# MuffinSchematic.net
KiCad netlist of a schematic drawn in EasyEDA
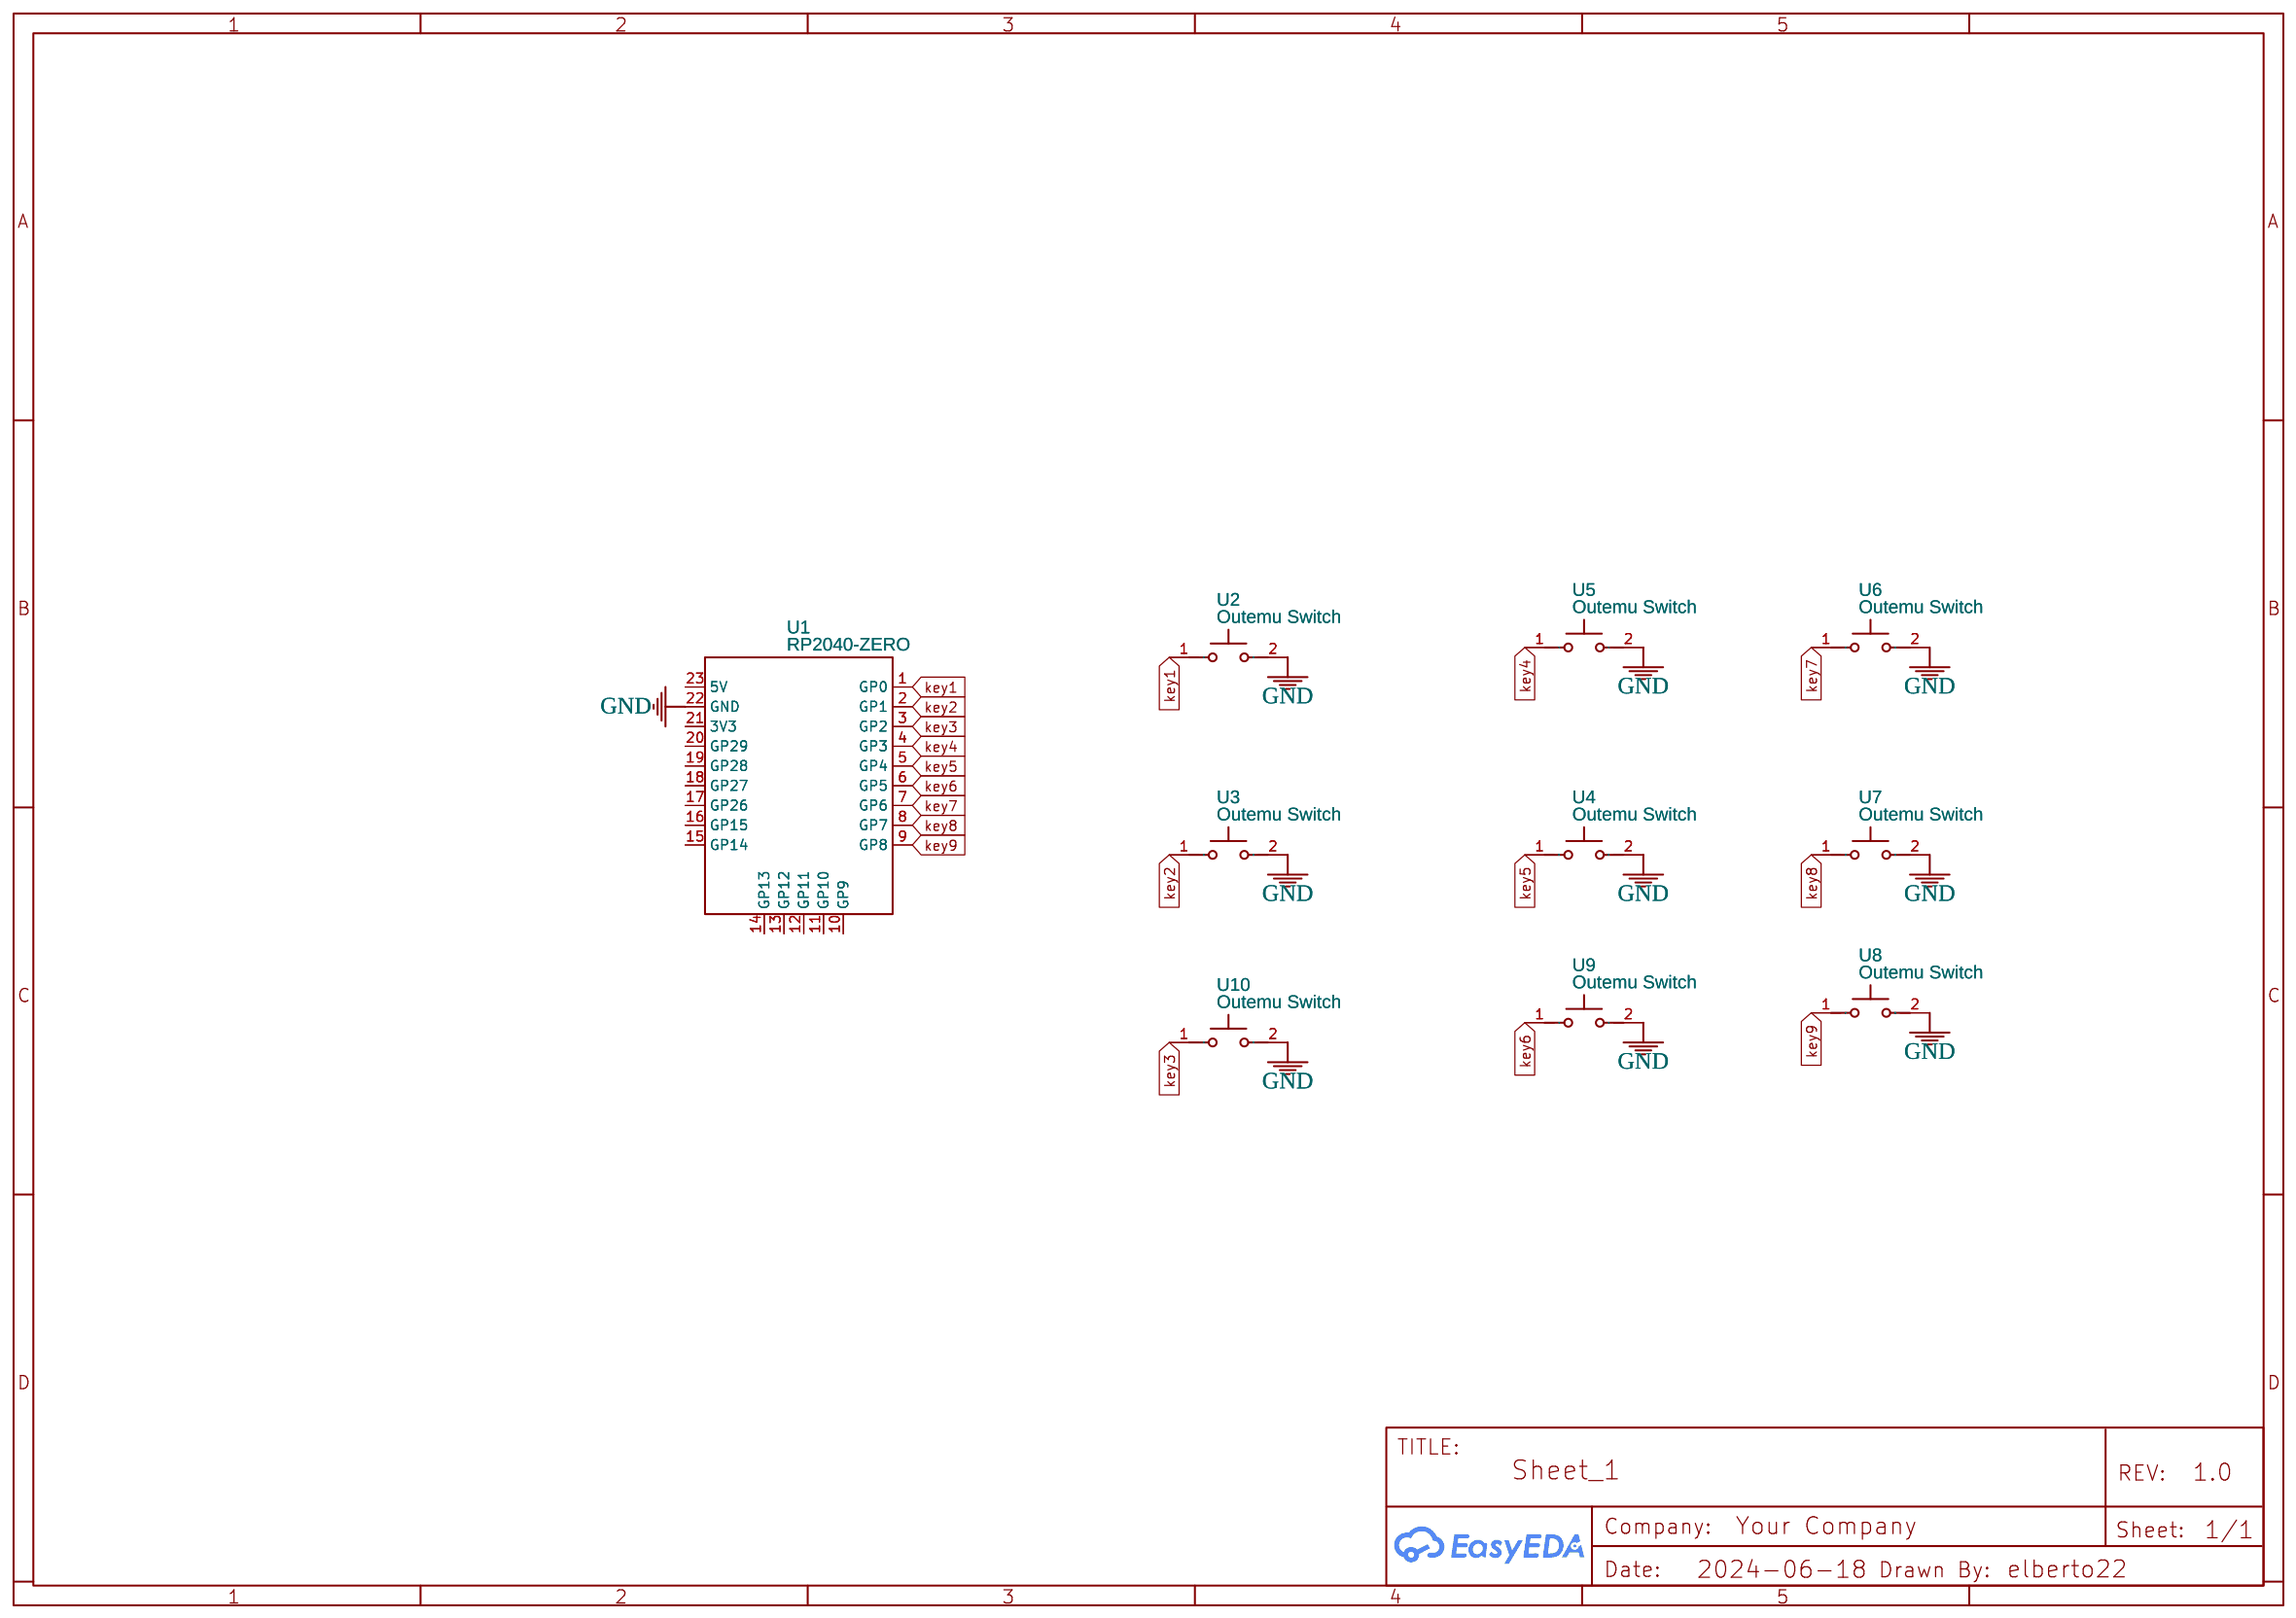
[diagram p0: schematic sheet]

(export (version "E")
  (design (tool "Eeschema 10.0.6"))
  (components
    (comp (ref "U1")
      (value "RP2040-ZERO")
      (fields
        (field (name "Manufacturer Part") "RP2040-Zero")
        (field (name "Manufacturer") "Waveshare(微雪电子)")
      )
      (libsource (lib "") (part "RP2040-ZERO"))
    )
    (comp (ref "U2")
      (value "Outemu Switch")
      (fields (field (name "Manufacturer") "HepLer"))
      (libsource (lib "") (part "Outemu Switch"))
    )
    (comp (ref "U3")
      (value "Outemu Switch")
      (fields (field (name "Manufacturer") "HepLer"))
      (libsource (lib "") (part "Outemu Switch"))
    )
    (comp (ref "U4")
      (value "Outemu Switch")
      (fields (field (name "Manufacturer") "HepLer"))
      (libsource (lib "") (part "Outemu Switch"))
    )
    (comp (ref "U5")
      (value "Outemu Switch")
      (fields (field (name "Manufacturer") "HepLer"))
      (libsource (lib "") (part "Outemu Switch"))
    )
    (comp (ref "U6")
      (value "Outemu Switch")
      (fields (field (name "Manufacturer") "HepLer"))
      (libsource (lib "") (part "Outemu Switch"))
    )
    (comp (ref "U7")
      (value "Outemu Switch")
      (fields (field (name "Manufacturer") "HepLer"))
      (libsource (lib "") (part "Outemu Switch"))
    )
    (comp (ref "U8")
      (value "Outemu Switch")
      (fields (field (name "Manufacturer") "HepLer"))
      (libsource (lib "") (part "Outemu Switch"))
    )
    (comp (ref "U9")
      (value "Outemu Switch")
      (fields (field (name "Manufacturer") "HepLer"))
      (libsource (lib "") (part "Outemu Switch"))
    )
    (comp (ref "U10")
      (value "Outemu Switch")
      (fields (field (name "Manufacturer") "HepLer"))
      (libsource (lib "") (part "Outemu Switch"))
    )
  )
  (nets
    (net (code "1") (name "GND") (class "Default")
      (node (ref "U1") (pin "22") (pinfunction "GND_22") (pintype "unspecified"))
      (node (ref "U10") (pin "2") (pinfunction "2_2") (pintype "unspecified"))
      (node (ref "U2") (pin "2") (pinfunction "2_2") (pintype "unspecified"))
      (node (ref "U3") (pin "2") (pinfunction "2_2") (pintype "unspecified"))
      (node (ref "U4") (pin "2") (pinfunction "2_2") (pintype "unspecified"))
      (node (ref "U5") (pin "2") (pinfunction "2_2") (pintype "unspecified"))
      (node (ref "U6") (pin "2") (pinfunction "2_2") (pintype "unspecified"))
      (node (ref "U7") (pin "2") (pinfunction "2_2") (pintype "unspecified"))
      (node (ref "U8") (pin "2") (pinfunction "2_2") (pintype "unspecified"))
      (node (ref "U9") (pin "2") (pinfunction "2_2") (pintype "unspecified"))
    )
    (net (code "2") (name "key1") (class "Default")
      (node (ref "U1") (pin "1") (pinfunction "GP0_1") (pintype "unspecified"))
      (node (ref "U2") (pin "1") (pinfunction "1_1") (pintype "unspecified"))
    )
    (net (code "3") (name "key2") (class "Default")
      (node (ref "U1") (pin "2") (pinfunction "GP1_2") (pintype "unspecified"))
      (node (ref "U3") (pin "1") (pinfunction "1_1") (pintype "unspecified"))
    )
    (net (code "4") (name "key3") (class "Default")
      (node (ref "U1") (pin "3") (pinfunction "GP2_3") (pintype "unspecified"))
      (node (ref "U10") (pin "1") (pinfunction "1_1") (pintype "unspecified"))
    )
    (net (code "5") (name "key4") (class "Default")
      (node (ref "U1") (pin "4") (pinfunction "GP3_4") (pintype "unspecified"))
      (node (ref "U5") (pin "1") (pinfunction "1_1") (pintype "unspecified"))
    )
    (net (code "6") (name "key5") (class "Default")
      (node (ref "U1") (pin "5") (pinfunction "GP4_5") (pintype "unspecified"))
      (node (ref "U4") (pin "1") (pinfunction "1_1") (pintype "unspecified"))
    )
    (net (code "7") (name "key6") (class "Default")
      (node (ref "U1") (pin "6") (pinfunction "GP5_6") (pintype "unspecified"))
      (node (ref "U9") (pin "1") (pinfunction "1_1") (pintype "unspecified"))
    )
    (net (code "8") (name "key7") (class "Default")
      (node (ref "U1") (pin "7") (pinfunction "GP6_7") (pintype "unspecified"))
      (node (ref "U6") (pin "1") (pinfunction "1_1") (pintype "unspecified"))
    )
    (net (code "9") (name "key8") (class "Default")
      (node (ref "U1") (pin "8") (pinfunction "GP7_8") (pintype "unspecified"))
      (node (ref "U7") (pin "1") (pinfunction "1_1") (pintype "unspecified"))
    )
    (net (code "10") (name "key9") (class "Default")
      (node (ref "U1") (pin "9") (pinfunction "GP8_9") (pintype "unspecified"))
      (node (ref "U8") (pin "1") (pinfunction "1_1") (pintype "unspecified"))
    )
    (net (code "11") (name "unconnected-(U1-3V3-Pad21)") (class "Default")
      (node (ref "U1") (pin "21") (pinfunction "3V3_21") (pintype "unspecified"))
    )
    (net (code "12") (name "unconnected-(U1-5V-Pad23)") (class "Default")
      (node (ref "U1") (pin "23") (pinfunction "5V_23") (pintype "unspecified"))
    )
    (net (code "13") (name "unconnected-(U1-GP9-Pad10)") (class "Default")
      (node (ref "U1") (pin "10") (pinfunction "GP9_10") (pintype "unspecified"))
    )
    (net (code "14") (name "unconnected-(U1-GP10-Pad11)") (class "Default")
      (node (ref "U1") (pin "11") (pinfunction "GP10_11") (pintype "unspecified"))
    )
    (net (code "15") (name "unconnected-(U1-GP11-Pad12)") (class "Default")
      (node (ref "U1") (pin "12") (pinfunction "GP11_12") (pintype "unspecified"))
    )
    (net (code "16") (name "unconnected-(U1-GP12-Pad13)") (class "Default")
      (node (ref "U1") (pin "13") (pinfunction "GP12_13") (pintype "unspecified"))
    )
    (net (code "17") (name "unconnected-(U1-GP13-Pad14)") (class "Default")
      (node (ref "U1") (pin "14") (pinfunction "GP13_14") (pintype "unspecified"))
    )
    (net (code "18") (name "unconnected-(U1-GP14-Pad15)") (class "Default")
      (node (ref "U1") (pin "15") (pinfunction "GP14_15") (pintype "unspecified"))
    )
    (net (code "19") (name "unconnected-(U1-GP15-Pad16)") (class "Default")
      (node (ref "U1") (pin "16") (pinfunction "GP15_16") (pintype "unspecified"))
    )
    (net (code "20") (name "unconnected-(U1-GP26-Pad17)") (class "Default")
      (node (ref "U1") (pin "17") (pinfunction "GP26_17") (pintype "unspecified"))
    )
    (net (code "21") (name "unconnected-(U1-GP27-Pad18)") (class "Default")
      (node (ref "U1") (pin "18") (pinfunction "GP27_18") (pintype "unspecified"))
    )
    (net (code "22") (name "unconnected-(U1-GP28-Pad19)") (class "Default")
      (node (ref "U1") (pin "19") (pinfunction "GP28_19") (pintype "unspecified"))
    )
    (net (code "23") (name "unconnected-(U1-GP29-Pad20)") (class "Default")
      (node (ref "U1") (pin "20") (pinfunction "GP29_20") (pintype "unspecified"))
    )
  )
)
